# board.net
KiCad netlist of a schematic drawn in EAGLE
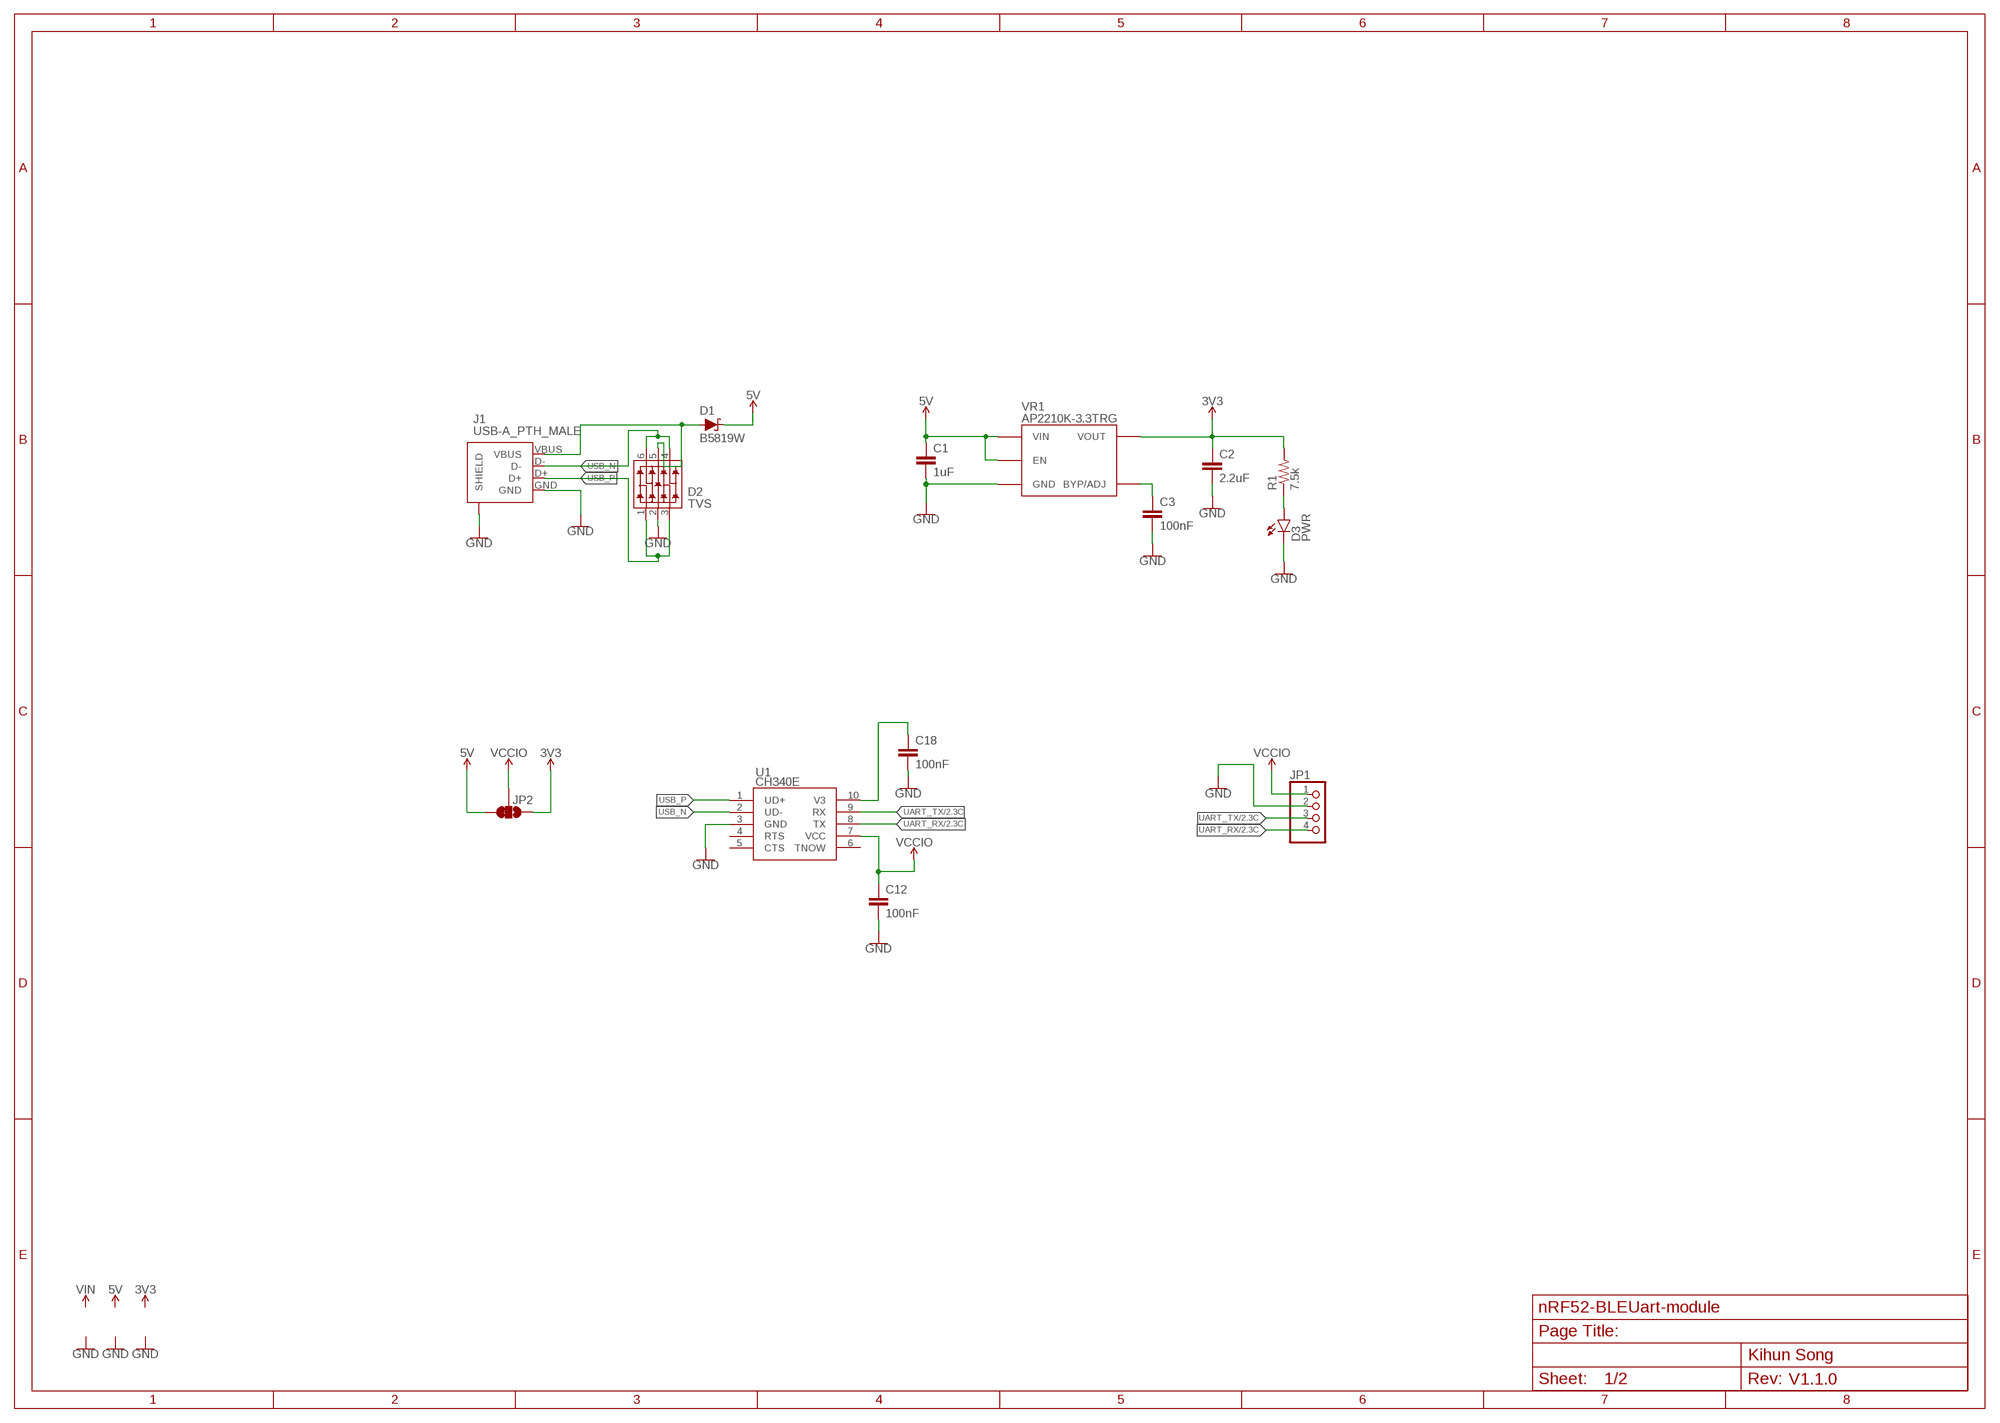
[diagram p0: schematic, sheet 1]
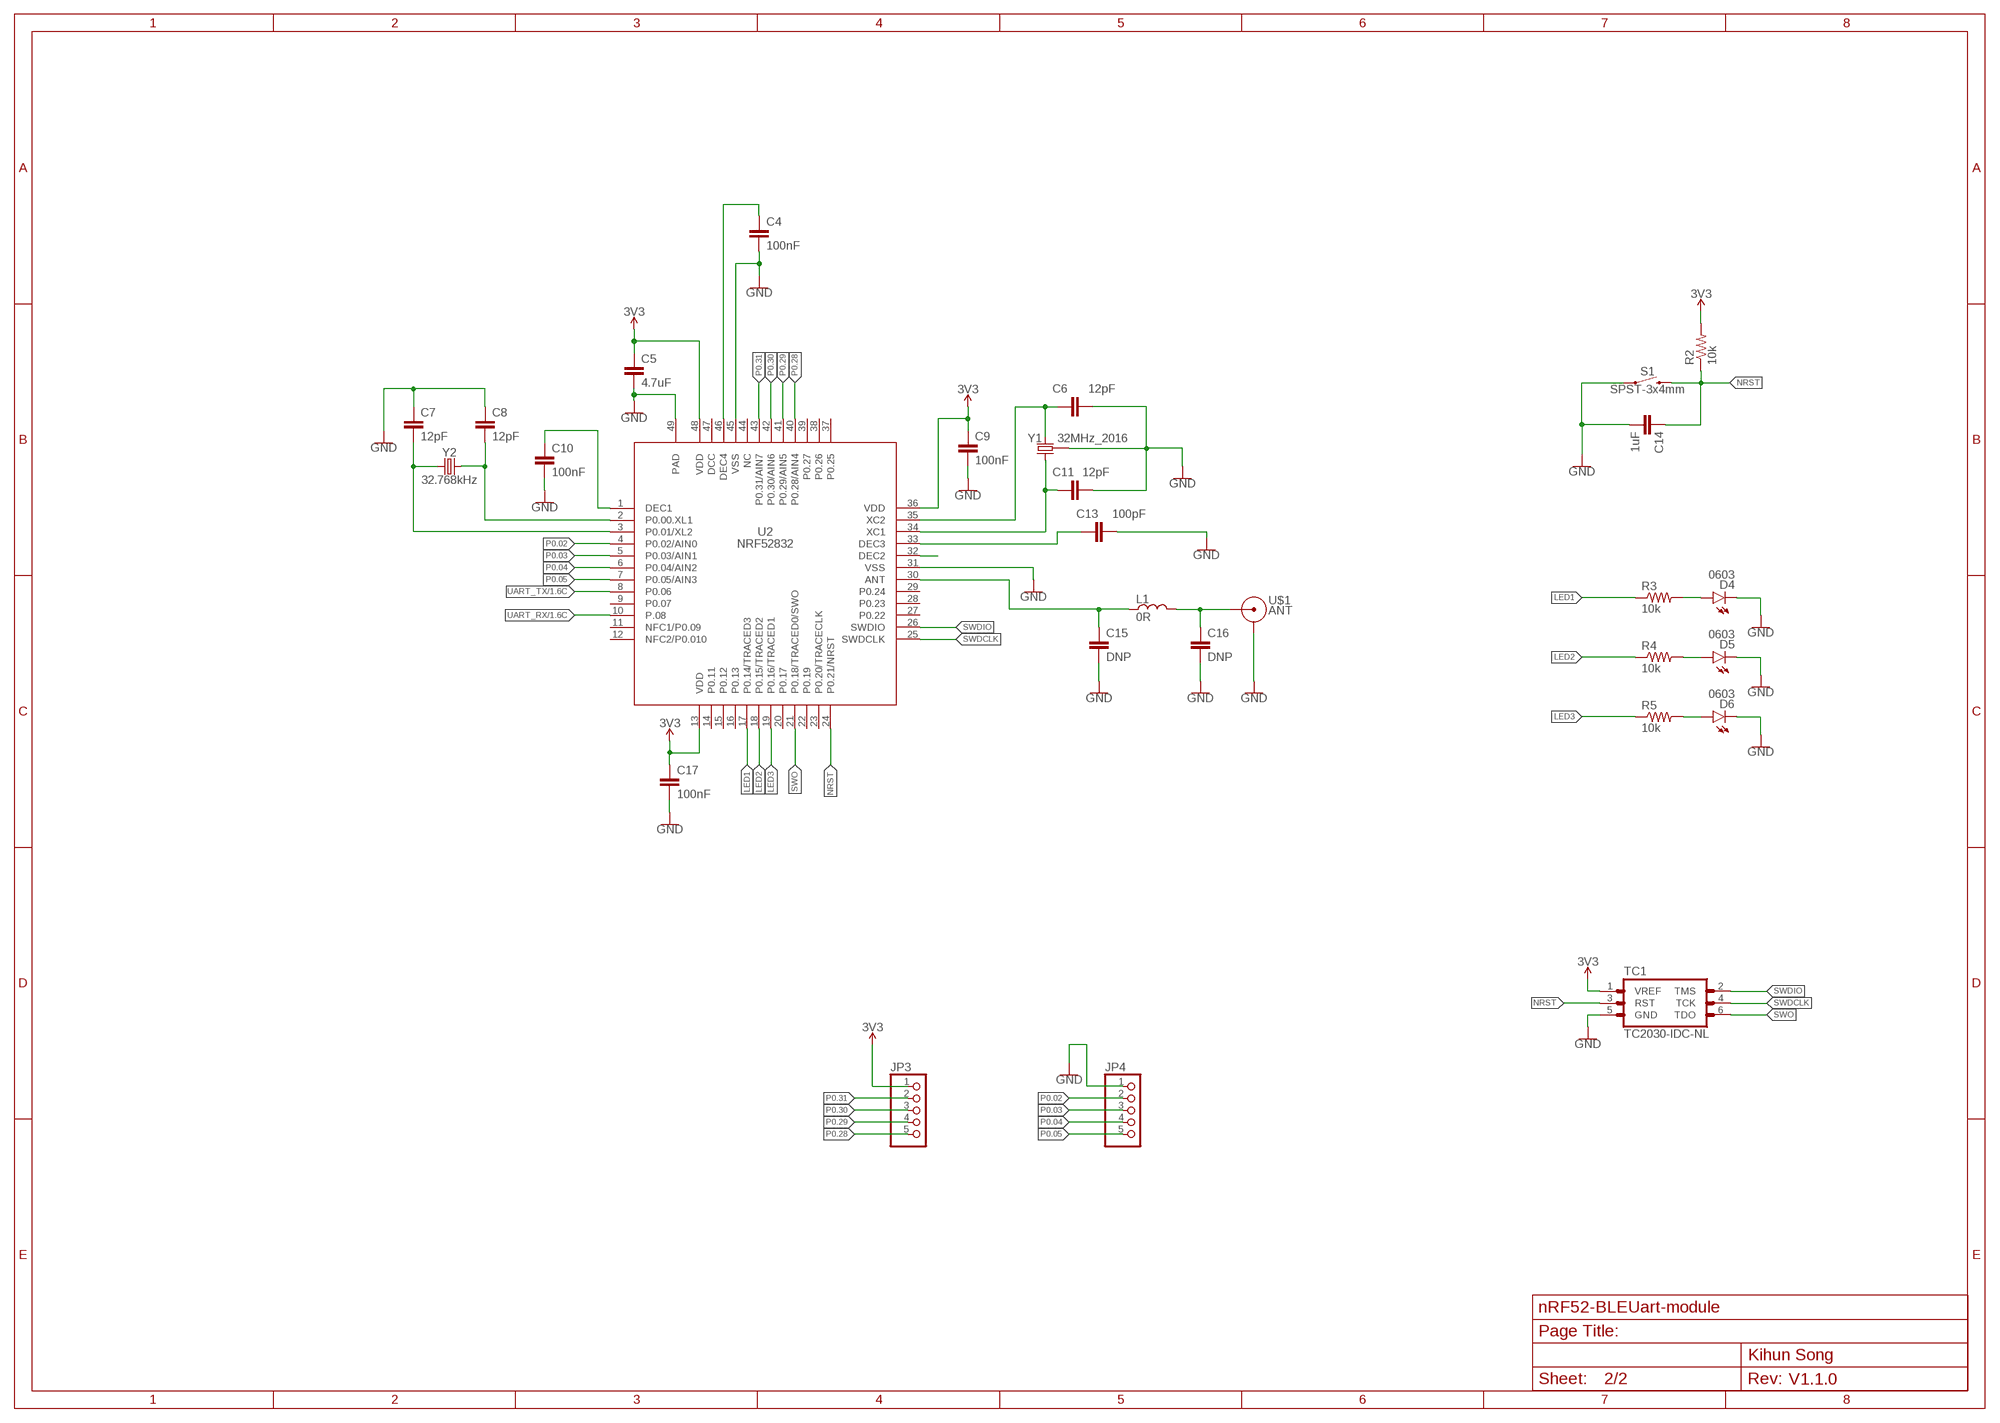
[diagram p1: schematic, sheet 2]

(export (version "E")
  (design (tool "Eeschema 10.0.6"))
  (components
    (comp (ref "C4")
      (value "100nF")
      (footprint "eagle-import:C0402")
      (libsource (lib "eagle-import") (part "C-NON-POLC0402"))
    )
    (comp (ref "C5")
      (value "4.7uF")
      (footprint "eagle-import:C0402")
      (libsource (lib "eagle-import") (part "C-NON-POLC0402"))
    )
    (comp (ref "C6")
      (value "12pF")
      (footprint "eagle-import:C0402")
      (libsource (lib "eagle-import") (part "C-NON-POLC0402"))
    )
    (comp (ref "C7")
      (value "12pF")
      (footprint "eagle-import:C0402")
      (libsource (lib "eagle-import") (part "C-NON-POLC0402"))
    )
    (comp (ref "C8")
      (value "12pF")
      (footprint "eagle-import:C0402")
      (libsource (lib "eagle-import") (part "C-NON-POLC0402"))
    )
    (comp (ref "C9")
      (value "100nF")
      (footprint "eagle-import:C0402")
      (libsource (lib "eagle-import") (part "C-NON-POLC0402"))
    )
    (comp (ref "C10")
      (value "100nF")
      (footprint "eagle-import:C0402")
      (libsource (lib "eagle-import") (part "C-NON-POLC0402"))
    )
    (comp (ref "C11")
      (value "12pF")
      (footprint "eagle-import:C0402")
      (libsource (lib "eagle-import") (part "C-NON-POLC0402"))
    )
    (comp (ref "C13")
      (value "100pF")
      (footprint "eagle-import:C0402")
      (libsource (lib "eagle-import") (part "C-NON-POLC0402"))
    )
    (comp (ref "C14")
      (value "1uF")
      (footprint "eagle-import:C0402")
      (libsource (lib "eagle-import") (part "C-NON-POLC0402"))
    )
    (comp (ref "C15")
      (value "DNP")
      (footprint "eagle-import:C0402")
      (libsource (lib "eagle-import") (part "C-NON-POLC0402"))
    )
    (comp (ref "C16")
      (value "DNP")
      (footprint "eagle-import:C0402")
      (libsource (lib "eagle-import") (part "C-NON-POLC0402"))
    )
    (comp (ref "C17")
      (value "100nF")
      (footprint "eagle-import:C0402")
      (libsource (lib "eagle-import") (part "C-NON-POLC0402"))
    )
    (comp (ref "D4")
      (value "0603")
      (footprint "eagle-import:LED_0603")
      (libsource (lib "eagle-import") (part "LED_0603"))
    )
    (comp (ref "D5")
      (value "0603")
      (footprint "eagle-import:LED_0603")
      (libsource (lib "eagle-import") (part "LED_0603"))
    )
    (comp (ref "D6")
      (value "0603")
      (footprint "eagle-import:LED_0603")
      (libsource (lib "eagle-import") (part "LED_0603"))
    )
    (comp (ref "JP3")
      (value "PINHD-1X5-NOSILK")
      (footprint "eagle-import:1X05-NOSILK")
      (libsource (lib "eagle-import") (part "PINHD-1X5-NOSILK"))
    )
    (comp (ref "JP4")
      (value "PINHD-1X5-NOSILK")
      (footprint "eagle-import:1X05-NOSILK")
      (libsource (lib "eagle-import") (part "PINHD-1X5-NOSILK"))
    )
    (comp (ref "L1")
      (value "0R")
      (footprint "eagle-import:R0402")
      (libsource (lib "eagle-import") (part "L0402"))
    )
    (comp (ref "R2")
      (value "10k")
      (footprint "eagle-import:R0402")
      (libsource (lib "eagle-import") (part "RR0402"))
    )
    (comp (ref "R3")
      (value "10k")
      (footprint "eagle-import:R0402")
      (libsource (lib "eagle-import") (part "RR0402"))
    )
    (comp (ref "R4")
      (value "10k")
      (footprint "eagle-import:R0402")
      (libsource (lib "eagle-import") (part "RR0402"))
    )
    (comp (ref "R5")
      (value "10k")
      (footprint "eagle-import:R0402")
      (libsource (lib "eagle-import") (part "RR0402"))
    )
    (comp (ref "S1")
      (value "SPST-3x4mm")
      (footprint "eagle-import:TACTILE_SWITCH_SMD_3.0X4.0MM")
      (libsource (lib "eagle-import") (part "SWITCH-SPST-SMD-3.0X4.0MM"))
    )
    (comp (ref "TC1")
      (value "TC2030-IDC-NL")
      (footprint "eagle-import:TC2030-IDC-NL")
      (libsource (lib "eagle-import") (part "TC2030-IDC-NL"))
    )
    (comp (ref "U$1")
      (value "ANT")
      (footprint "eagle-import:TI-AN043_LEFT_SHORTER")
      (libsource (lib "eagle-import") (part "INVERTED_F_2.4GHZ_TI-AN043_L_SHORT"))
    )
    (comp (ref "U2")
      (value "NRF52832")
      (footprint "eagle-import:QFN40P600X600X90-49T450N")
      (libsource (lib "eagle-import") (part "NRF52832"))
    )
    (comp (ref "Y1")
      (value "32MHz_2016")
      (footprint "eagle-import:CRYSTAL-SMD-2.0X1.6MM")
      (libsource (lib "eagle-import") (part "CRYSTAL-2.0X1.6MM"))
    )
    (comp (ref "Y2")
      (value "32.768kHz")
      (footprint "eagle-import:CRYSTAL-SMD-3.2X1.5MM")
      (libsource (lib "eagle-import") (part "CRYSTAL-32.768KHZ_3215"))
    )
    (comp (ref "C1")
      (value "1uF")
      (footprint "eagle-import:C0402")
      (libsource (lib "eagle-import") (part "C-NON-POLC0402"))
    )
    (comp (ref "C2")
      (value "2.2uF")
      (footprint "eagle-import:C0603")
      (libsource (lib "eagle-import") (part "C-NON-POLC0603"))
    )
    (comp (ref "C3")
      (value "100nF")
      (footprint "eagle-import:C0402")
      (libsource (lib "eagle-import") (part "C-NON-POLC0402"))
    )
    (comp (ref "C12")
      (value "100nF")
      (footprint "eagle-import:C0402")
      (libsource (lib "eagle-import") (part "C-NON-POLC0402"))
    )
    (comp (ref "C18")
      (value "100nF")
      (footprint "eagle-import:C0402")
      (libsource (lib "eagle-import") (part "C-NON-POLC0402"))
    )
    (comp (ref "D1")
      (value "B5819W")
      (footprint "eagle-import:SOD-123")
      (libsource (lib "eagle-import") (part "DIODE-SCHOTTKY_SOD-123"))
    )
    (comp (ref "D2")
      (value "TVS")
      (footprint "eagle-import:SPT-23-6")
      (libsource (lib "eagle-import") (part "TVS-ARRAY_SOT-23-6"))
    )
    (comp (ref "D3")
      (value "PWR")
      (footprint "eagle-import:LED_0603")
      (libsource (lib "eagle-import") (part "LED_0603"))
    )
    (comp (ref "J1")
      (value "USB-A_PTH_MALE")
      (footprint "eagle-import:USB-A-H-RECT")
      (libsource (lib "eagle-import") (part "USB-A_PTH_MALE-U-G-O4DD-W-1"))
    )
    (comp (ref "JP1")
      (value "Rx Tx G V")
      (footprint "eagle-import:1X04-NOSILK")
      (libsource (lib "eagle-import") (part "PINHD-1X4NOSILK"))
    )
    (comp (ref "JP2")
      (value "5V 3V3")
      (footprint "eagle-import:SMT-JUMPER_3_1-NC_TRACE_NO-SILK")
      (libsource (lib "eagle-import") (part "JUMPER-SMT_3_1-NC_TRACE_NO-SILK"))
    )
    (comp (ref "R1")
      (value "7.5k")
      (footprint "eagle-import:R0402")
      (libsource (lib "eagle-import") (part "RR0402"))
    )
    (comp (ref "U1")
      (value "CH340E")
      (footprint "eagle-import:MSOP-10")
      (libsource (lib "eagle-import") (part "CH340E"))
    )
    (comp (ref "VR1")
      (value "AP2210K-3.3TRG")
      (footprint "eagle-import:SOT-23-5")
      (libsource (lib "eagle-import") (part "AP2210K"))
    )
  )
  (nets
    (net (code "1") (name "3V3") (class "Default")
      (node (ref "C17") (pin "1") (pinfunction "1_1") (pintype "passive"))
      (node (ref "C2") (pin "1") (pinfunction "1_1") (pintype "passive"))
      (node (ref "C5") (pin "1") (pinfunction "1_1") (pintype "passive"))
      (node (ref "C9") (pin "1") (pinfunction "1_1") (pintype "passive"))
      (node (ref "JP2") (pin "1") (pinfunction "1_1") (pintype "passive"))
      (node (ref "JP3") (pin "1") (pinfunction "1_1") (pintype "passive"))
      (node (ref "R1") (pin "2") (pinfunction "2_2") (pintype "passive"))
      (node (ref "R2") (pin "2") (pinfunction "2_2") (pintype "passive"))
      (node (ref "TC1") (pin "1") (pinfunction "VREF_1") (pintype "passive"))
      (node (ref "U2") (pin "13") (pinfunction "VDD_13") (pintype "bidirectional"))
      (node (ref "U2") (pin "36") (pinfunction "VDD_36") (pintype "bidirectional"))
      (node (ref "U2") (pin "48") (pinfunction "VDD_48") (pintype "bidirectional"))
      (node (ref "VR1") (pin "5") (pinfunction "VOUT_5") (pintype "output"))
    )
    (net (code "2") (name "5V") (class "Default")
      (node (ref "C1") (pin "1") (pinfunction "1_1") (pintype "passive"))
      (node (ref "D1") (pin "C") (pinfunction "C_C") (pintype "passive"))
      (node (ref "JP2") (pin "3") (pinfunction "3_3") (pintype "passive"))
      (node (ref "VR1") (pin "1") (pinfunction "VIN_1") (pintype "input"))
      (node (ref "VR1") (pin "3") (pinfunction "EN_3") (pintype "bidirectional"))
    )
    (net (code "3") (name "GND") (class "Default")
      (node (ref "C1") (pin "2") (pinfunction "2_2") (pintype "passive"))
      (node (ref "C10") (pin "2") (pinfunction "2_2") (pintype "passive"))
      (node (ref "C11") (pin "2") (pinfunction "2_2") (pintype "passive"))
      (node (ref "C12") (pin "2") (pinfunction "2_2") (pintype "passive"))
      (node (ref "C13") (pin "2") (pinfunction "2_2") (pintype "passive"))
      (node (ref "C14") (pin "2") (pinfunction "2_2") (pintype "passive"))
      (node (ref "C15") (pin "2") (pinfunction "2_2") (pintype "passive"))
      (node (ref "C16") (pin "2") (pinfunction "2_2") (pintype "passive"))
      (node (ref "C17") (pin "2") (pinfunction "2_2") (pintype "passive"))
      (node (ref "C18") (pin "2") (pinfunction "2_2") (pintype "passive"))
      (node (ref "C2") (pin "2") (pinfunction "2_2") (pintype "passive"))
      (node (ref "C3") (pin "2") (pinfunction "2_2") (pintype "passive"))
      (node (ref "C4") (pin "2") (pinfunction "2_2") (pintype "passive"))
      (node (ref "C5") (pin "2") (pinfunction "2_2") (pintype "passive"))
      (node (ref "C6") (pin "2") (pinfunction "2_2") (pintype "passive"))
      (node (ref "C7") (pin "1") (pinfunction "1_1") (pintype "passive"))
      (node (ref "C8") (pin "1") (pinfunction "1_1") (pintype "passive"))
      (node (ref "C9") (pin "2") (pinfunction "2_2") (pintype "passive"))
      (node (ref "D2") (pin "2") (pinfunction "VSS_2") (pintype "bidirectional"))
      (node (ref "D3") (pin "C") (pinfunction "C_C") (pintype "passive"))
      (node (ref "D4") (pin "C") (pinfunction "C_C") (pintype "passive"))
      (node (ref "D5") (pin "C") (pinfunction "C_C") (pintype "passive"))
      (node (ref "D6") (pin "C") (pinfunction "C_C") (pintype "passive"))
      (node (ref "J1") (pin "GND") (pinfunction "GND_GND") (pintype "power_in"))
      (node (ref "J1") (pin "SHIELD@0") (pinfunction "SHIELD_SHIELD@0") (pintype "bidirectional"))
      (node (ref "J1") (pin "SHIELD@1") (pinfunction "SHIELD_SHIELD@1") (pintype "bidirectional"))
      (node (ref "J1") (pin "SHIELD@2") (pinfunction "SHIELD_SHIELD@2") (pintype "bidirectional"))
      (node (ref "J1") (pin "SHIELD@3") (pinfunction "SHIELD_SHIELD@3") (pintype "bidirectional"))
      (node (ref "JP1") (pin "2") (pinfunction "2_2") (pintype "passive"))
      (node (ref "JP4") (pin "1") (pinfunction "1_1") (pintype "passive"))
      (node (ref "S1") (pin "1") (pinfunction "1_1") (pintype "passive"))
      (node (ref "TC1") (pin "5") (pinfunction "GND_5") (pintype "passive"))
      (node (ref "U$1") (pin "GND") (pinfunction "GND_GND") (pintype "bidirectional"))
      (node (ref "U1") (pin "3") (pinfunction "GND_3") (pintype "power_in"))
      (node (ref "U2") (pin "31") (pinfunction "VSS_31") (pintype "bidirectional"))
      (node (ref "U2") (pin "45") (pinfunction "VSS_45") (pintype "bidirectional"))
      (node (ref "U2") (pin "49") (pinfunction "PAD_49") (pintype "bidirectional"))
      (node (ref "VR1") (pin "2") (pinfunction "GND_2") (pintype "power_in"))
      (node (ref "Y1") (pin "2") (pinfunction "GND_2") (pintype "power_in"))
      (node (ref "Y1") (pin "4") (pinfunction "GND_4") (pintype "power_in"))
    )
    (net (code "4") (name "LED1") (class "Default")
      (node (ref "R3") (pin "1") (pinfunction "1_1") (pintype "passive"))
      (node (ref "U2") (pin "17") (pinfunction "P0.14/TRACED3_17") (pintype "bidirectional"))
    )
    (net (code "5") (name "LED2") (class "Default")
      (node (ref "R4") (pin "1") (pinfunction "1_1") (pintype "passive"))
      (node (ref "U2") (pin "18") (pinfunction "P0.15/TRACED2_18") (pintype "bidirectional"))
    )
    (net (code "6") (name "LED3") (class "Default")
      (node (ref "R5") (pin "1") (pinfunction "1_1") (pintype "passive"))
      (node (ref "U2") (pin "19") (pinfunction "P0.16/TRACED1_19") (pintype "bidirectional"))
    )
    (net (code "7") (name "NRST") (class "Default")
      (node (ref "C14") (pin "1") (pinfunction "1_1") (pintype "passive"))
      (node (ref "R2") (pin "1") (pinfunction "1_1") (pintype "passive"))
      (node (ref "S1") (pin "2") (pinfunction "2_2") (pintype "passive"))
      (node (ref "TC1") (pin "3") (pinfunction "RST_3") (pintype "passive"))
      (node (ref "U2") (pin "24") (pinfunction "P0.21/NRST_24") (pintype "bidirectional"))
    )
    (net (code "8") (name "Net-(D2-VCC)") (class "Default")
      (node (ref "D1") (pin "A") (pinfunction "A_A") (pintype "passive"))
      (node (ref "D2") (pin "5") (pinfunction "VCC_5") (pintype "bidirectional"))
      (node (ref "J1") (pin "VBUS") (pinfunction "VBUS_VBUS") (pintype "power_in"))
    )
    (net (code "9") (name "Net-(D3-PadA)") (class "Default")
      (node (ref "D3") (pin "A") (pinfunction "A_A") (pintype "passive"))
      (node (ref "R1") (pin "1") (pinfunction "1_1") (pintype "passive"))
    )
    (net (code "10") (name "Net-(D4-PadA)") (class "Default")
      (node (ref "D4") (pin "A") (pinfunction "A_A") (pintype "passive"))
      (node (ref "R3") (pin "2") (pinfunction "2_2") (pintype "passive"))
    )
    (net (code "11") (name "Net-(D5-PadA)") (class "Default")
      (node (ref "D5") (pin "A") (pinfunction "A_A") (pintype "passive"))
      (node (ref "R4") (pin "2") (pinfunction "2_2") (pintype "passive"))
    )
    (net (code "12") (name "Net-(D6-PadA)") (class "Default")
      (node (ref "D6") (pin "A") (pinfunction "A_A") (pintype "passive"))
      (node (ref "R5") (pin "2") (pinfunction "2_2") (pintype "passive"))
    )
    (net (code "13") (name "Net-(U$1-FEED)") (class "Default")
      (node (ref "C16") (pin "1") (pinfunction "1_1") (pintype "passive"))
      (node (ref "L1") (pin "2") (pinfunction "2_2") (pintype "passive"))
      (node (ref "U$1") (pin "RF") (pinfunction "FEED_RF") (pintype "bidirectional"))
    )
    (net (code "14") (name "Net-(U1-V3)") (class "Default")
      (node (ref "C18") (pin "1") (pinfunction "1_1") (pintype "passive"))
      (node (ref "U1") (pin "10") (pinfunction "V3_10") (pintype "power_in"))
    )
    (net (code "15") (name "Net-(U2-ANT)") (class "Default")
      (node (ref "C15") (pin "1") (pinfunction "1_1") (pintype "passive"))
      (node (ref "L1") (pin "1") (pinfunction "1_1") (pintype "passive"))
      (node (ref "U2") (pin "30") (pinfunction "ANT_30") (pintype "bidirectional"))
    )
    (net (code "16") (name "Net-(U2-DEC1)") (class "Default")
      (node (ref "C10") (pin "1") (pinfunction "1_1") (pintype "passive"))
      (node (ref "U2") (pin "1") (pinfunction "DEC1_1") (pintype "bidirectional"))
    )
    (net (code "17") (name "Net-(U2-DEC3)") (class "Default")
      (node (ref "C13") (pin "1") (pinfunction "1_1") (pintype "passive"))
      (node (ref "U2") (pin "33") (pinfunction "DEC3_33") (pintype "bidirectional"))
    )
    (net (code "18") (name "Net-(U2-DEC4)") (class "Default")
      (node (ref "C4") (pin "1") (pinfunction "1_1") (pintype "passive"))
      (node (ref "U2") (pin "46") (pinfunction "DEC4_46") (pintype "bidirectional"))
    )
    (net (code "19") (name "Net-(U2-P0.00.XL1)") (class "Default")
      (node (ref "C8") (pin "2") (pinfunction "2_2") (pintype "passive"))
      (node (ref "U2") (pin "2") (pinfunction "P0.00.XL1_2") (pintype "bidirectional"))
      (node (ref "Y2") (pin "P$2") (pinfunction "2_P$2") (pintype "passive"))
    )
    (net (code "20") (name "Net-(U2-P0.01{slash}XL2)") (class "Default")
      (node (ref "C7") (pin "2") (pinfunction "2_2") (pintype "passive"))
      (node (ref "U2") (pin "3") (pinfunction "P0.01/XL2_3") (pintype "bidirectional"))
      (node (ref "Y2") (pin "P$1") (pinfunction "1_P$1") (pintype "passive"))
    )
    (net (code "21") (name "Net-(U2-XC1)") (class "Default")
      (node (ref "C11") (pin "1") (pinfunction "1_1") (pintype "passive"))
      (node (ref "U2") (pin "34") (pinfunction "XC1_34") (pintype "bidirectional"))
      (node (ref "Y1") (pin "1") (pinfunction "1_1") (pintype "passive"))
    )
    (net (code "22") (name "Net-(U2-XC2)") (class "Default")
      (node (ref "C6") (pin "1") (pinfunction "1_1") (pintype "passive"))
      (node (ref "U2") (pin "35") (pinfunction "XC2_35") (pintype "bidirectional"))
      (node (ref "Y1") (pin "3") (pinfunction "2_3") (pintype "passive"))
    )
    (net (code "23") (name "Net-(VR1-BYP{slash}ADJ)") (class "Default")
      (node (ref "C3") (pin "1") (pinfunction "1_1") (pintype "passive"))
      (node (ref "VR1") (pin "4") (pinfunction "BYP/ADJ_4") (pintype "bidirectional"))
    )
    (net (code "24") (name "P0.02") (class "Default")
      (node (ref "JP4") (pin "2") (pinfunction "2_2") (pintype "passive"))
      (node (ref "U2") (pin "4") (pinfunction "P0.02/AIN0_4") (pintype "bidirectional"))
    )
    (net (code "25") (name "P0.03") (class "Default")
      (node (ref "JP4") (pin "3") (pinfunction "3_3") (pintype "passive"))
      (node (ref "U2") (pin "5") (pinfunction "P0.03/AIN1_5") (pintype "bidirectional"))
    )
    (net (code "26") (name "P0.04") (class "Default")
      (node (ref "JP4") (pin "4") (pinfunction "4_4") (pintype "passive"))
      (node (ref "U2") (pin "6") (pinfunction "P0.04/AIN2_6") (pintype "bidirectional"))
    )
    (net (code "27") (name "P0.05") (class "Default")
      (node (ref "JP4") (pin "5") (pinfunction "5_5") (pintype "passive"))
      (node (ref "U2") (pin "7") (pinfunction "P0.05/AIN3_7") (pintype "bidirectional"))
    )
    (net (code "28") (name "P0.28") (class "Default")
      (node (ref "JP3") (pin "5") (pinfunction "5_5") (pintype "passive"))
      (node (ref "U2") (pin "40") (pinfunction "P0.28/AIN4_40") (pintype "bidirectional"))
    )
    (net (code "29") (name "P0.29") (class "Default")
      (node (ref "JP3") (pin "4") (pinfunction "4_4") (pintype "passive"))
      (node (ref "U2") (pin "41") (pinfunction "P0.29/AIN5_41") (pintype "bidirectional"))
    )
    (net (code "30") (name "P0.30") (class "Default")
      (node (ref "JP3") (pin "3") (pinfunction "3_3") (pintype "passive"))
      (node (ref "U2") (pin "42") (pinfunction "P0.30/AIN6_42") (pintype "bidirectional"))
    )
    (net (code "31") (name "P0.31") (class "Default")
      (node (ref "JP3") (pin "2") (pinfunction "2_2") (pintype "passive"))
      (node (ref "U2") (pin "43") (pinfunction "P0.31/AIN7_43") (pintype "bidirectional"))
    )
    (net (code "32") (name "SWDCLK") (class "Default")
      (node (ref "TC1") (pin "4") (pinfunction "TCK_4") (pintype "passive"))
      (node (ref "U2") (pin "25") (pinfunction "SWDCLK_25") (pintype "bidirectional"))
    )
    (net (code "33") (name "SWDIO") (class "Default")
      (node (ref "TC1") (pin "2") (pinfunction "TMS_2") (pintype "passive"))
      (node (ref "U2") (pin "26") (pinfunction "SWDIO_26") (pintype "bidirectional"))
    )
    (net (code "34") (name "SWO") (class "Default")
      (node (ref "TC1") (pin "6") (pinfunction "TDO_6") (pintype "passive"))
      (node (ref "U2") (pin "21") (pinfunction "P0.18/TRACED0/SWO_21") (pintype "bidirectional"))
    )
    (net (code "35") (name "UART_RX") (class "Default")
      (node (ref "JP1") (pin "4") (pinfunction "4_4") (pintype "passive"))
      (node (ref "U1") (pin "8") (pinfunction "TX_8") (pintype "output"))
      (node (ref "U2") (pin "10") (pinfunction "P.08_10") (pintype "bidirectional"))
    )
    (net (code "36") (name "UART_TX") (class "Default")
      (node (ref "JP1") (pin "3") (pinfunction "3_3") (pintype "passive"))
      (node (ref "U1") (pin "9") (pinfunction "RX_9") (pintype "input"))
      (node (ref "U2") (pin "8") (pinfunction "P0.06_8") (pintype "bidirectional"))
    )
    (net (code "37") (name "USB_N") (class "Default")
      (node (ref "D2") (pin "4") (pinfunction "IO3_4") (pintype "bidirectional"))
      (node (ref "D2") (pin "6") (pinfunction "IO4_6") (pintype "bidirectional"))
      (node (ref "J1") (pin "D-") (pinfunction "D-_D-") (pintype "bidirectional"))
      (node (ref "U1") (pin "2") (pinfunction "UD-_2") (pintype "bidirectional"))
    )
    (net (code "38") (name "USB_P") (class "Default")
      (node (ref "D2") (pin "1") (pinfunction "IO1_1") (pintype "bidirectional"))
      (node (ref "D2") (pin "3") (pinfunction "IO2_3") (pintype "bidirectional"))
      (node (ref "J1") (pin "D+") (pinfunction "D+_D+") (pintype "bidirectional"))
      (node (ref "U1") (pin "1") (pinfunction "UD+_1") (pintype "bidirectional"))
    )
    (net (code "39") (name "VCCIO") (class "Default")
      (node (ref "C12") (pin "1") (pinfunction "1_1") (pintype "passive"))
      (node (ref "JP1") (pin "1") (pinfunction "1_1") (pintype "passive"))
      (node (ref "JP2") (pin "2") (pinfunction "2_2") (pintype "passive"))
      (node (ref "U1") (pin "7") (pinfunction "VCC_7") (pintype "power_in"))
    )
    (net (code "41") (name "unconnected-(U1-CTS-Pad5)") (class "Default")
      (node (ref "U1") (pin "5") (pinfunction "CTS_5") (pintype "input"))
    )
    (net (code "42") (name "unconnected-(U1-RTS-Pad4)") (class "Default")
      (node (ref "U1") (pin "4") (pinfunction "RTS_4") (pintype "output"))
    )
    (net (code "43") (name "unconnected-(U1-TNOW-Pad6)") (class "Default")
      (node (ref "U1") (pin "6") (pinfunction "TNOW_6") (pintype "output"))
    )
    (net (code "44") (name "unconnected-(U2-DCC-Pad47)") (class "Default")
      (node (ref "U2") (pin "47") (pinfunction "DCC_47") (pintype "bidirectional"))
    )
    (net (code "45") (name "unconnected-(U2-DEC2-Pad32)") (class "Default")
      (node (ref "U2") (pin "32") (pinfunction "DEC2_32") (pintype "bidirectional"))
    )
    (net (code "46") (name "unconnected-(U2-NC-Pad44)") (class "Default")
      (node (ref "U2") (pin "44") (pinfunction "NC_44") (pintype "no_connect"))
    )
    (net (code "47") (name "unconnected-(U2-NFC1{slash}P0.09-Pad11)") (class "Default")
      (node (ref "U2") (pin "11") (pinfunction "NFC1/P0.09_11") (pintype "bidirectional"))
    )
    (net (code "48") (name "unconnected-(U2-NFC2{slash}P0.010-Pad12)") (class "Default")
      (node (ref "U2") (pin "12") (pinfunction "NFC2/P0.010_12") (pintype "bidirectional"))
    )
    (net (code "49") (name "unconnected-(U2-P0.07-Pad9)") (class "Default")
      (node (ref "U2") (pin "9") (pinfunction "P0.07_9") (pintype "bidirectional"))
    )
    (net (code "50") (name "unconnected-(U2-P0.11-Pad14)") (class "Default")
      (node (ref "U2") (pin "14") (pinfunction "P0.11_14") (pintype "bidirectional"))
    )
    (net (code "51") (name "unconnected-(U2-P0.12-Pad15)") (class "Default")
      (node (ref "U2") (pin "15") (pinfunction "P0.12_15") (pintype "bidirectional"))
    )
    (net (code "52") (name "unconnected-(U2-P0.13-Pad16)") (class "Default")
      (node (ref "U2") (pin "16") (pinfunction "P0.13_16") (pintype "bidirectional"))
    )
    (net (code "53") (name "unconnected-(U2-P0.17-Pad20)") (class "Default")
      (node (ref "U2") (pin "20") (pinfunction "P0.17_20") (pintype "bidirectional"))
    )
    (net (code "54") (name "unconnected-(U2-P0.19-Pad22)") (class "Default")
      (node (ref "U2") (pin "22") (pinfunction "P0.19_22") (pintype "bidirectional"))
    )
    (net (code "55") (name "unconnected-(U2-P0.20{slash}TRACECLK-Pad23)") (class "Default")
      (node (ref "U2") (pin "23") (pinfunction "P0.20/TRACECLK_23") (pintype "bidirectional"))
    )
    (net (code "56") (name "unconnected-(U2-P0.22-Pad27)") (class "Default")
      (node (ref "U2") (pin "27") (pinfunction "P0.22_27") (pintype "bidirectional"))
    )
    (net (code "57") (name "unconnected-(U2-P0.23-Pad28)") (class "Default")
      (node (ref "U2") (pin "28") (pinfunction "P0.23_28") (pintype "bidirectional"))
    )
    (net (code "58") (name "unconnected-(U2-P0.24-Pad29)") (class "Default")
      (node (ref "U2") (pin "29") (pinfunction "P0.24_29") (pintype "bidirectional"))
    )
    (net (code "59") (name "unconnected-(U2-P0.25-Pad37)") (class "Default")
      (node (ref "U2") (pin "37") (pinfunction "P0.25_37") (pintype "bidirectional"))
    )
    (net (code "60") (name "unconnected-(U2-P0.26-Pad38)") (class "Default")
      (node (ref "U2") (pin "38") (pinfunction "P0.26_38") (pintype "bidirectional"))
    )
    (net (code "61") (name "unconnected-(U2-P0.27-Pad39)") (class "Default")
      (node (ref "U2") (pin "39") (pinfunction "P0.27_39") (pintype "bidirectional"))
    )
  )
)
